# Esquematic.net
KiCad netlist of a schematic drawn in EAGLE
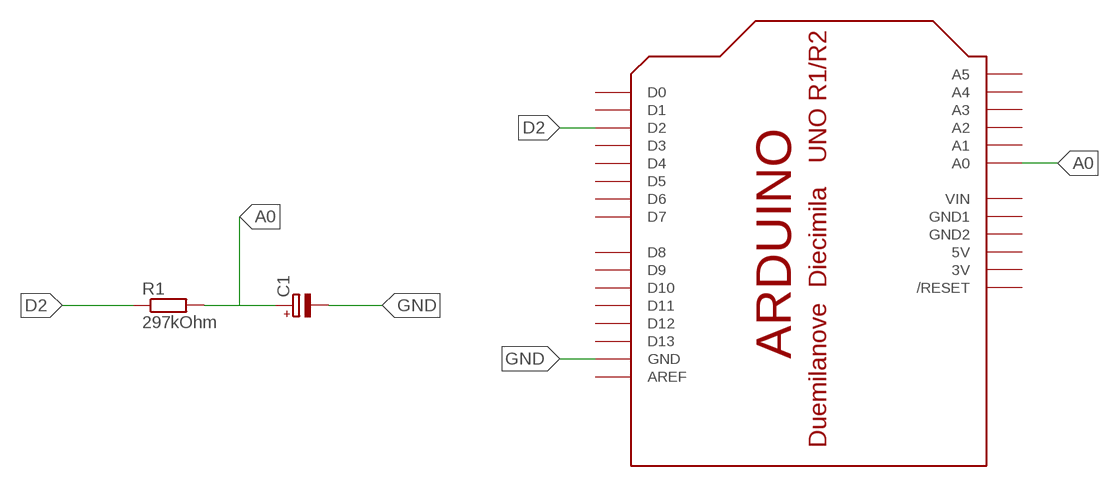
[diagram p0: schematic, sheet 1]

(export (version "E")
  (design (tool "Eeschema 10.0.6"))
  (components
    (comp (ref "C1")
      (value "CPOL-EUE5-13")
      (footprint "eagle-import:E5-13")
      (libsource (lib "eagle-import") (part "CPOL-EUE5-13"))
    )
    (comp (ref "R1")
      (value "297kOhm")
      (footprint "eagle-import:0207_10")
      (libsource (lib "eagle-import") (part "R-EU_0207/10"))
    )
    (comp (ref "U$1")
      (value "ARDUINOUNO")
      (footprint "eagle-import:ARDUINO")
      (libsource (lib "eagle-import") (part "ARDUINOUNO"))
    )
  )
  (nets
    (net (code "1") (name "/3V") (class "Default")
      (node (ref "U$1") (pin "3V") (pinfunction "3V_3V") (pintype "power_in"))
    )
    (net (code "2") (name "/5V") (class "Default")
      (node (ref "U$1") (pin "5V") (pinfunction "5V_5V") (pintype "power_in"))
    )
    (net (code "3") (name "/GND1") (class "Default")
      (node (ref "U$1") (pin "GND1") (pinfunction "GND1_GND1") (pintype "power_in"))
    )
    (net (code "4") (name "/GND2") (class "Default")
      (node (ref "U$1") (pin "GND2") (pinfunction "GND2_GND2") (pintype "power_in"))
    )
    (net (code "5") (name "/VIN") (class "Default")
      (node (ref "U$1") (pin "VIN") (pinfunction "VIN_VIN") (pintype "power_in"))
    )
    (net (code "6") (name "A0") (class "Default")
      (node (ref "U$1") (pin "A0") (pinfunction "A0_A0") (pintype "bidirectional"))
    )
    (net (code "7") (name "D2") (class "Default")
      (node (ref "R1") (pin "1") (pinfunction "1_1") (pintype "passive"))
      (node (ref "U$1") (pin "D2") (pinfunction "D2_D2") (pintype "bidirectional"))
    )
    (net (code "8") (name "GND") (class "Default")
      (node (ref "C1") (pin "-") (pinfunction "-_-") (pintype "passive"))
      (node (ref "U$1") (pin "GND") (pinfunction "GND_GND") (pintype "power_in"))
    )
    (net (code "9") (name "Net-(C1-Pad+)") (class "Default")
      (node (ref "C1") (pin "+") (pinfunction "+_+") (pintype "passive"))
      (node (ref "R1") (pin "2") (pinfunction "2_2") (pintype "passive"))
    )
    (net (code "10") (name "unconnected-(U$1-PadA1)") (class "Default")
      (node (ref "U$1") (pin "A1") (pinfunction "A1_A1") (pintype "bidirectional"))
    )
    (net (code "11") (name "unconnected-(U$1-PadA2)") (class "Default")
      (node (ref "U$1") (pin "A2") (pinfunction "A2_A2") (pintype "bidirectional"))
    )
    (net (code "12") (name "unconnected-(U$1-PadA3)") (class "Default")
      (node (ref "U$1") (pin "A3") (pinfunction "A3_A3") (pintype "bidirectional"))
    )
    (net (code "13") (name "unconnected-(U$1-PadA4)") (class "Default")
      (node (ref "U$1") (pin "A4") (pinfunction "A4_A4") (pintype "bidirectional"))
    )
    (net (code "14") (name "unconnected-(U$1-PadA5)") (class "Default")
      (node (ref "U$1") (pin "A5") (pinfunction "A5_A5") (pintype "bidirectional"))
    )
    (net (code "15") (name "unconnected-(U$1-PadAREF)") (class "Default")
      (node (ref "U$1") (pin "AREF") (pinfunction "AREF_AREF") (pintype "bidirectional"))
    )
    (net (code "16") (name "unconnected-(U$1-PadD0)") (class "Default")
      (node (ref "U$1") (pin "D0") (pinfunction "D0_D0") (pintype "bidirectional"))
    )
    (net (code "17") (name "unconnected-(U$1-PadD1)") (class "Default")
      (node (ref "U$1") (pin "D1") (pinfunction "D1_D1") (pintype "bidirectional"))
    )
    (net (code "18") (name "unconnected-(U$1-PadD3)") (class "Default")
      (node (ref "U$1") (pin "D3") (pinfunction "D3_D3") (pintype "bidirectional"))
    )
    (net (code "19") (name "unconnected-(U$1-PadD4)") (class "Default")
      (node (ref "U$1") (pin "D4") (pinfunction "D4_D4") (pintype "bidirectional"))
    )
    (net (code "20") (name "unconnected-(U$1-PadD5)") (class "Default")
      (node (ref "U$1") (pin "D5") (pinfunction "D5_D5") (pintype "bidirectional"))
    )
    (net (code "21") (name "unconnected-(U$1-PadD6)") (class "Default")
      (node (ref "U$1") (pin "D6") (pinfunction "D6_D6") (pintype "bidirectional"))
    )
    (net (code "22") (name "unconnected-(U$1-PadD7)") (class "Default")
      (node (ref "U$1") (pin "D7") (pinfunction "D7_D7") (pintype "bidirectional"))
    )
    (net (code "23") (name "unconnected-(U$1-PadD8)") (class "Default")
      (node (ref "U$1") (pin "D8") (pinfunction "D8_D8") (pintype "bidirectional"))
    )
    (net (code "24") (name "unconnected-(U$1-PadD9)") (class "Default")
      (node (ref "U$1") (pin "D9") (pinfunction "D9_D9") (pintype "bidirectional"))
    )
    (net (code "25") (name "unconnected-(U$1-PadD10)") (class "Default")
      (node (ref "U$1") (pin "D10") (pinfunction "D10_D10") (pintype "bidirectional"))
    )
    (net (code "26") (name "unconnected-(U$1-PadD11)") (class "Default")
      (node (ref "U$1") (pin "D11") (pinfunction "D11_D11") (pintype "bidirectional"))
    )
    (net (code "27") (name "unconnected-(U$1-PadD12)") (class "Default")
      (node (ref "U$1") (pin "D12") (pinfunction "D12_D12") (pintype "bidirectional"))
    )
    (net (code "28") (name "unconnected-(U$1-PadD13)") (class "Default")
      (node (ref "U$1") (pin "D13") (pinfunction "D13_D13") (pintype "bidirectional"))
    )
    (net (code "29") (name "unconnected-(U$1-{slash}RESET-PadRESET)") (class "Default")
      (node (ref "U$1") (pin "RESET") (pinfunction "/RESET_RESET") (pintype "bidirectional"))
    )
  )
)
